# CRYO_ASIC_flex_40pin_adapter.net
KiCad netlist of a schematic drawn in Altium Designer
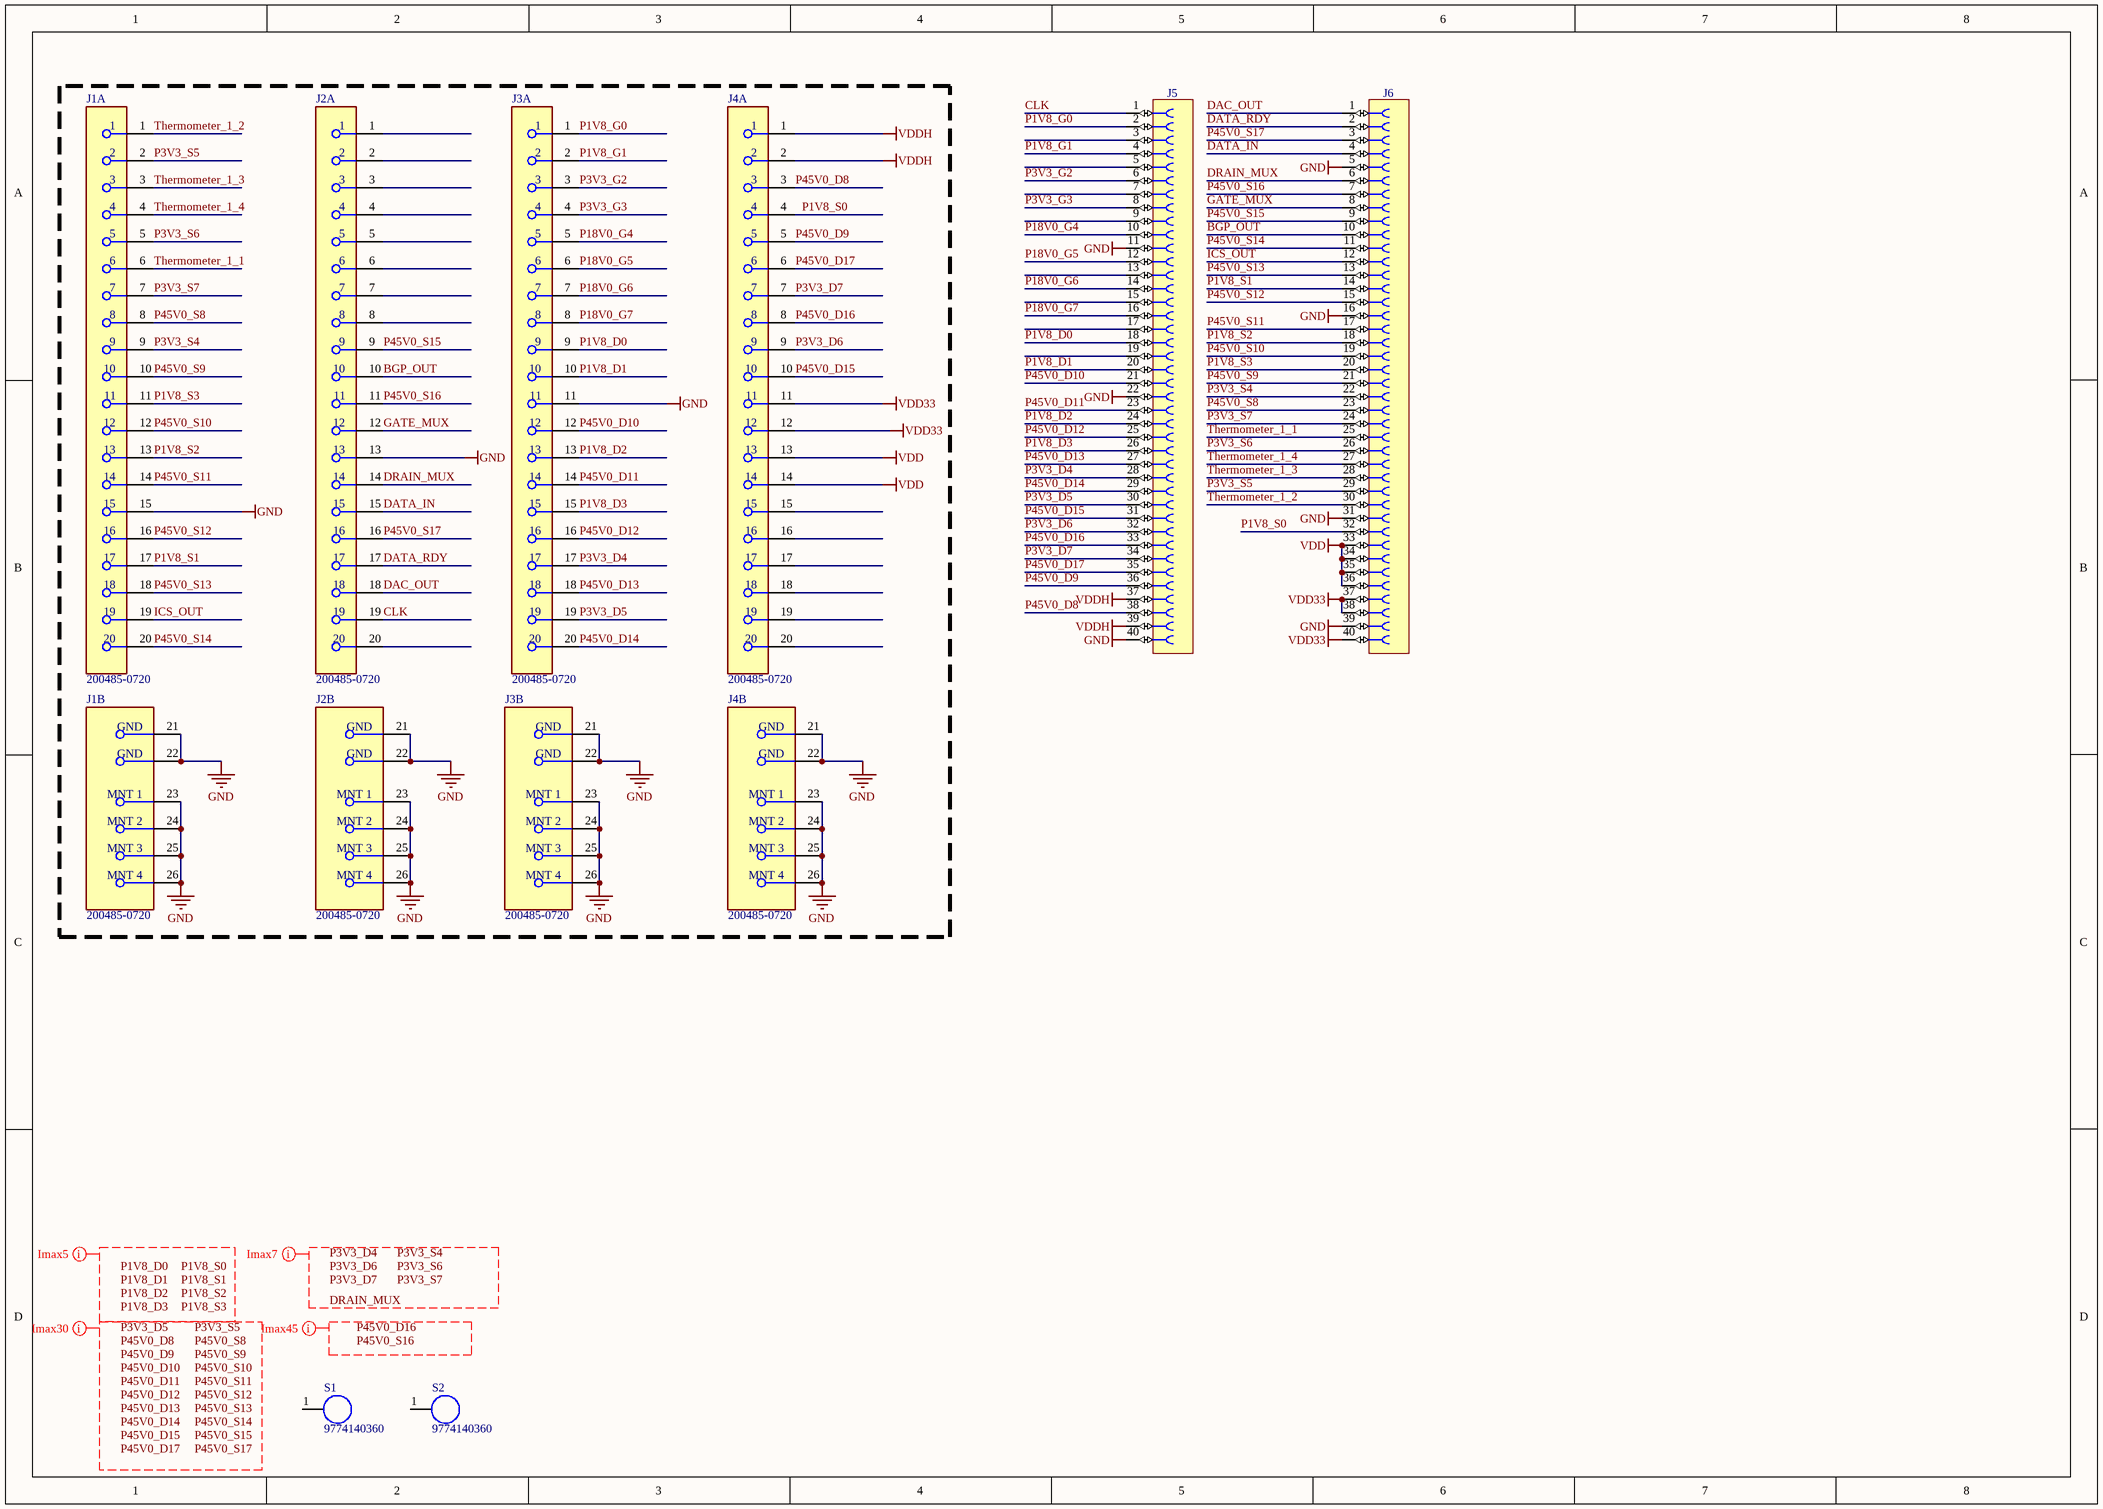
[diagram p0: CRYO_ASIC_flex_40pin_adapter.SchDoc]

(export (version "E")
  (design (tool "Eeschema 10.0.6"))
  (components
    (comp (ref "J1")
      (value "200485-0720")
      (footprint "FP-200485-0720-MFG")
      (description "0.5 ONE-TOUCH ST 20P GND")
      (libsource (lib "Altium Content Vault") (part "ad1b4d674f8db84ba9d04d6195ac6ba"))
    )
    (comp (ref "J2")
      (value "200485-0720")
      (footprint "FP-200485-0720-MFG")
      (description "0.5 ONE-TOUCH ST 20P GND")
      (libsource (lib "Altium Content Vault") (part "ad1b4d674f8db84ba9d04d6195ac6ba"))
    )
    (comp (ref "J3")
      (value "200485-0720")
      (footprint "FP-200485-0720-MFG")
      (description "0.5 ONE-TOUCH ST 20P GND")
      (libsource (lib "Altium Content Vault") (part "ad1b4d674f8db84ba9d04d6195ac6ba"))
    )
    (comp (ref "J4")
      (value "200485-0720")
      (footprint "FP-200485-0720-MFG")
      (description "0.5 ONE-TOUCH ST 20P GND")
      (libsource (lib "Altium Content Vault") (part "ad1b4d674f8db84ba9d04d6195ac6ba"))
    )
    (comp (ref "J5")
      (value "Socket 40")
      (footprint "SAMTEC_RSM-120-02-L-D-K-TR")
      (description "Connector 40 Female")
      (fields
        (field (name "PART NUMBER") "SAMTEC_RSM-120-02-L-D-K-TR")
        (field (name "MANUFACTURER") "SAMTEC")
        (field (name "AUTHOR") "CERN DEM JLC")
      )
      (libsource (lib "Connectors") (part "Connector 40 Female"))
    )
    (comp (ref "J6")
      (value "Socket 40")
      (footprint "SAMTEC_RSM-120-02-L-D-K-TR")
      (description "Connector 40 Female")
      (fields
        (field (name "PART NUMBER") "SAMTEC_RSM-120-02-L-D-K-TR")
        (field (name "MANUFACTURER") "SAMTEC")
        (field (name "AUTHOR") "CERN DEM JLC")
      )
      (libsource (lib "Connectors") (part "Connector 40 Female"))
    )
    (comp (ref "S1")
      (value "9774140360")
      (footprint "9774140360")
      (description "WA-SMSI SMD Steel Spacer with internal Thread")
      (fields (field (name "MANUFACTURER") "Wurth Elektronik") (field (name "CREATED BY") "Baojun Chen"))
      (libsource (lib "Altium_SMSI_SMT_STEEL_SPACER_M2_5_THREAD_INTERNAL_rev15a") (part "WA-SMSI,  9774140360"))
    )
    (comp (ref "S2")
      (value "9774140360")
      (footprint "9774140360")
      (description "WA-SMSI SMD Steel Spacer with internal Thread")
      (fields (field (name "MANUFACTURER") "Wurth Elektronik") (field (name "CREATED BY") "Baojun Chen"))
      (libsource (lib "Altium_SMSI_SMT_STEEL_SPACER_M2_5_THREAD_INTERNAL_rev15a") (part "WA-SMSI,  9774140360"))
    )
  )
  (nets
    (net (code "1") (name "/BGP_OUT") (class "Default")
      (node (ref "J2") (pin "10") (pinfunction "10_10") (pintype "passive"))
      (node (ref "J6") (pin "10") (pinfunction "10_10") (pintype "bidirectional"))
    )
    (net (code "2") (name "/CLK") (class "Default")
      (node (ref "J2") (pin "19") (pinfunction "19_19") (pintype "passive"))
      (node (ref "J5") (pin "1") (pinfunction "1_1") (pintype "bidirectional"))
    )
    (net (code "3") (name "/DAC_OUT") (class "Default")
      (node (ref "J2") (pin "18") (pinfunction "18_18") (pintype "passive"))
      (node (ref "J6") (pin "1") (pinfunction "1_1") (pintype "bidirectional"))
    )
    (net (code "4") (name "/DATA_IN") (class "Default")
      (node (ref "J2") (pin "15") (pinfunction "15_15") (pintype "passive"))
      (node (ref "J6") (pin "4") (pinfunction "4_4") (pintype "bidirectional"))
    )
    (net (code "5") (name "/DATA_RDY") (class "Default")
      (node (ref "J2") (pin "17") (pinfunction "17_17") (pintype "passive"))
      (node (ref "J6") (pin "2") (pinfunction "2_2") (pintype "bidirectional"))
    )
    (net (code "6") (name "/DRAIN_MUX") (class "Default")
      (node (ref "J2") (pin "14") (pinfunction "14_14") (pintype "passive"))
      (node (ref "J6") (pin "6") (pinfunction "6_6") (pintype "bidirectional"))
    )
    (net (code "7") (name "/GATE_MUX") (class "Default")
      (node (ref "J2") (pin "12") (pinfunction "12_12") (pintype "passive"))
      (node (ref "J6") (pin "8") (pinfunction "8_8") (pintype "bidirectional"))
    )
    (net (code "8") (name "/ICS_OUT") (class "Default")
      (node (ref "J1") (pin "19") (pinfunction "19_19") (pintype "passive"))
      (node (ref "J6") (pin "12") (pinfunction "12_12") (pintype "bidirectional"))
    )
    (net (code "9") (name "/P1V8_D0") (class "Default")
      (node (ref "J3") (pin "9") (pinfunction "9_9") (pintype "passive"))
      (node (ref "J5") (pin "18") (pinfunction "18_18") (pintype "bidirectional"))
    )
    (net (code "10") (name "/P1V8_D1") (class "Default")
      (node (ref "J3") (pin "10") (pinfunction "10_10") (pintype "passive"))
      (node (ref "J5") (pin "20") (pinfunction "20_20") (pintype "bidirectional"))
    )
    (net (code "11") (name "/P1V8_D2") (class "Default")
      (node (ref "J3") (pin "13") (pinfunction "13_13") (pintype "passive"))
      (node (ref "J5") (pin "24") (pinfunction "24_24") (pintype "bidirectional"))
    )
    (net (code "12") (name "/P1V8_D3") (class "Default")
      (node (ref "J3") (pin "15") (pinfunction "15_15") (pintype "passive"))
      (node (ref "J5") (pin "26") (pinfunction "26_26") (pintype "bidirectional"))
    )
    (net (code "13") (name "/P1V8_G0") (class "Default")
      (node (ref "J3") (pin "1") (pinfunction "1_1") (pintype "passive"))
      (node (ref "J5") (pin "2") (pinfunction "2_2") (pintype "bidirectional"))
    )
    (net (code "14") (name "/P1V8_G1") (class "Default")
      (node (ref "J3") (pin "2") (pinfunction "2_2") (pintype "passive"))
      (node (ref "J5") (pin "4") (pinfunction "4_4") (pintype "bidirectional"))
    )
    (net (code "15") (name "/P1V8_S0") (class "Default")
      (node (ref "J4") (pin "4") (pinfunction "4_4") (pintype "passive"))
      (node (ref "J6") (pin "32") (pinfunction "32_32") (pintype "bidirectional"))
    )
    (net (code "16") (name "/P1V8_S1") (class "Default")
      (node (ref "J1") (pin "17") (pinfunction "17_17") (pintype "passive"))
      (node (ref "J6") (pin "14") (pinfunction "14_14") (pintype "bidirectional"))
    )
    (net (code "17") (name "/P1V8_S2") (class "Default")
      (node (ref "J1") (pin "13") (pinfunction "13_13") (pintype "passive"))
      (node (ref "J6") (pin "18") (pinfunction "18_18") (pintype "bidirectional"))
    )
    (net (code "18") (name "/P1V8_S3") (class "Default")
      (node (ref "J1") (pin "11") (pinfunction "11_11") (pintype "passive"))
      (node (ref "J6") (pin "20") (pinfunction "20_20") (pintype "bidirectional"))
    )
    (net (code "19") (name "/P3V3_D4") (class "Default")
      (node (ref "J3") (pin "17") (pinfunction "17_17") (pintype "passive"))
      (node (ref "J5") (pin "28") (pinfunction "28_28") (pintype "bidirectional"))
    )
    (net (code "20") (name "/P3V3_D5") (class "Default")
      (node (ref "J3") (pin "19") (pinfunction "19_19") (pintype "passive"))
      (node (ref "J5") (pin "30") (pinfunction "30_30") (pintype "bidirectional"))
    )
    (net (code "21") (name "/P3V3_D6") (class "Default")
      (node (ref "J4") (pin "9") (pinfunction "9_9") (pintype "passive"))
      (node (ref "J5") (pin "32") (pinfunction "32_32") (pintype "bidirectional"))
    )
    (net (code "22") (name "/P3V3_D7") (class "Default")
      (node (ref "J4") (pin "7") (pinfunction "7_7") (pintype "passive"))
      (node (ref "J5") (pin "34") (pinfunction "34_34") (pintype "bidirectional"))
    )
    (net (code "23") (name "/P3V3_G2") (class "Default")
      (node (ref "J3") (pin "3") (pinfunction "3_3") (pintype "passive"))
      (node (ref "J5") (pin "6") (pinfunction "6_6") (pintype "bidirectional"))
    )
    (net (code "24") (name "/P3V3_G3") (class "Default")
      (node (ref "J3") (pin "4") (pinfunction "4_4") (pintype "passive"))
      (node (ref "J5") (pin "8") (pinfunction "8_8") (pintype "bidirectional"))
    )
    (net (code "25") (name "/P3V3_S4") (class "Default")
      (node (ref "J1") (pin "9") (pinfunction "9_9") (pintype "passive"))
      (node (ref "J6") (pin "22") (pinfunction "22_22") (pintype "bidirectional"))
    )
    (net (code "26") (name "/P3V3_S5") (class "Default")
      (node (ref "J1") (pin "2") (pinfunction "2_2") (pintype "passive"))
      (node (ref "J6") (pin "29") (pinfunction "29_29") (pintype "bidirectional"))
    )
    (net (code "27") (name "/P3V3_S6") (class "Default")
      (node (ref "J1") (pin "5") (pinfunction "5_5") (pintype "passive"))
      (node (ref "J6") (pin "26") (pinfunction "26_26") (pintype "bidirectional"))
    )
    (net (code "28") (name "/P3V3_S7") (class "Default")
      (node (ref "J1") (pin "7") (pinfunction "7_7") (pintype "passive"))
      (node (ref "J6") (pin "24") (pinfunction "24_24") (pintype "bidirectional"))
    )
    (net (code "29") (name "/P18V0_G4") (class "Default")
      (node (ref "J3") (pin "5") (pinfunction "5_5") (pintype "passive"))
      (node (ref "J5") (pin "10") (pinfunction "10_10") (pintype "bidirectional"))
    )
    (net (code "30") (name "/P18V0_G5") (class "Default")
      (node (ref "J3") (pin "6") (pinfunction "6_6") (pintype "passive"))
      (node (ref "J5") (pin "12") (pinfunction "12_12") (pintype "bidirectional"))
    )
    (net (code "31") (name "/P18V0_G6") (class "Default")
      (node (ref "J3") (pin "7") (pinfunction "7_7") (pintype "passive"))
      (node (ref "J5") (pin "14") (pinfunction "14_14") (pintype "bidirectional"))
    )
    (net (code "32") (name "/P18V0_G7") (class "Default")
      (node (ref "J3") (pin "8") (pinfunction "8_8") (pintype "passive"))
      (node (ref "J5") (pin "16") (pinfunction "16_16") (pintype "bidirectional"))
    )
    (net (code "33") (name "/P45V0_D8") (class "Default")
      (node (ref "J4") (pin "3") (pinfunction "3_3") (pintype "passive"))
      (node (ref "J5") (pin "38") (pinfunction "38_38") (pintype "bidirectional"))
    )
    (net (code "34") (name "/P45V0_D9") (class "Default")
      (node (ref "J4") (pin "5") (pinfunction "5_5") (pintype "passive"))
      (node (ref "J5") (pin "36") (pinfunction "36_36") (pintype "bidirectional"))
    )
    (net (code "35") (name "/P45V0_D10") (class "Default")
      (node (ref "J3") (pin "12") (pinfunction "12_12") (pintype "passive"))
      (node (ref "J5") (pin "21") (pinfunction "21_21") (pintype "bidirectional"))
    )
    (net (code "36") (name "/P45V0_D11") (class "Default")
      (node (ref "J3") (pin "14") (pinfunction "14_14") (pintype "passive"))
      (node (ref "J5") (pin "23") (pinfunction "23_23") (pintype "bidirectional"))
    )
    (net (code "37") (name "/P45V0_D12") (class "Default")
      (node (ref "J3") (pin "16") (pinfunction "16_16") (pintype "passive"))
      (node (ref "J5") (pin "25") (pinfunction "25_25") (pintype "bidirectional"))
    )
    (net (code "38") (name "/P45V0_D13") (class "Default")
      (node (ref "J3") (pin "18") (pinfunction "18_18") (pintype "passive"))
      (node (ref "J5") (pin "27") (pinfunction "27_27") (pintype "bidirectional"))
    )
    (net (code "39") (name "/P45V0_D14") (class "Default")
      (node (ref "J3") (pin "20") (pinfunction "20_20") (pintype "passive"))
      (node (ref "J5") (pin "29") (pinfunction "29_29") (pintype "bidirectional"))
    )
    (net (code "40") (name "/P45V0_D15") (class "Default")
      (node (ref "J4") (pin "10") (pinfunction "10_10") (pintype "passive"))
      (node (ref "J5") (pin "31") (pinfunction "31_31") (pintype "bidirectional"))
    )
    (net (code "41") (name "/P45V0_D16") (class "Default")
      (node (ref "J4") (pin "8") (pinfunction "8_8") (pintype "passive"))
      (node (ref "J5") (pin "33") (pinfunction "33_33") (pintype "bidirectional"))
    )
    (net (code "42") (name "/P45V0_D17") (class "Default")
      (node (ref "J4") (pin "6") (pinfunction "6_6") (pintype "passive"))
      (node (ref "J5") (pin "35") (pinfunction "35_35") (pintype "bidirectional"))
    )
    (net (code "43") (name "/P45V0_S8") (class "Default")
      (node (ref "J1") (pin "8") (pinfunction "8_8") (pintype "passive"))
      (node (ref "J6") (pin "23") (pinfunction "23_23") (pintype "bidirectional"))
    )
    (net (code "44") (name "/P45V0_S9") (class "Default")
      (node (ref "J1") (pin "10") (pinfunction "10_10") (pintype "passive"))
      (node (ref "J6") (pin "21") (pinfunction "21_21") (pintype "bidirectional"))
    )
    (net (code "45") (name "/P45V0_S10") (class "Default")
      (node (ref "J1") (pin "12") (pinfunction "12_12") (pintype "passive"))
      (node (ref "J6") (pin "19") (pinfunction "19_19") (pintype "bidirectional"))
    )
    (net (code "46") (name "/P45V0_S11") (class "Default")
      (node (ref "J1") (pin "14") (pinfunction "14_14") (pintype "passive"))
      (node (ref "J6") (pin "17") (pinfunction "17_17") (pintype "bidirectional"))
    )
    (net (code "47") (name "/P45V0_S12") (class "Default")
      (node (ref "J1") (pin "16") (pinfunction "16_16") (pintype "passive"))
      (node (ref "J6") (pin "15") (pinfunction "15_15") (pintype "bidirectional"))
    )
    (net (code "48") (name "/P45V0_S13") (class "Default")
      (node (ref "J1") (pin "18") (pinfunction "18_18") (pintype "passive"))
      (node (ref "J6") (pin "13") (pinfunction "13_13") (pintype "bidirectional"))
    )
    (net (code "49") (name "/P45V0_S14") (class "Default")
      (node (ref "J1") (pin "20") (pinfunction "20_20") (pintype "passive"))
      (node (ref "J6") (pin "11") (pinfunction "11_11") (pintype "bidirectional"))
    )
    (net (code "50") (name "/P45V0_S15") (class "Default")
      (node (ref "J2") (pin "9") (pinfunction "9_9") (pintype "passive"))
      (node (ref "J6") (pin "9") (pinfunction "9_9") (pintype "bidirectional"))
    )
    (net (code "51") (name "/P45V0_S16") (class "Default")
      (node (ref "J2") (pin "11") (pinfunction "11_11") (pintype "passive"))
      (node (ref "J6") (pin "7") (pinfunction "7_7") (pintype "bidirectional"))
    )
    (net (code "52") (name "/P45V0_S17") (class "Default")
      (node (ref "J2") (pin "16") (pinfunction "16_16") (pintype "passive"))
      (node (ref "J6") (pin "3") (pinfunction "3_3") (pintype "bidirectional"))
    )
    (net (code "53") (name "/Thermometer_1_1") (class "Default")
      (node (ref "J1") (pin "6") (pinfunction "6_6") (pintype "passive"))
      (node (ref "J6") (pin "25") (pinfunction "25_25") (pintype "bidirectional"))
    )
    (net (code "54") (name "/Thermometer_1_2") (class "Default")
      (node (ref "J1") (pin "1") (pinfunction "1_1") (pintype "passive"))
      (node (ref "J6") (pin "30") (pinfunction "30_30") (pintype "bidirectional"))
    )
    (net (code "55") (name "/Thermometer_1_3") (class "Default")
      (node (ref "J1") (pin "3") (pinfunction "3_3") (pintype "passive"))
      (node (ref "J6") (pin "28") (pinfunction "28_28") (pintype "bidirectional"))
    )
    (net (code "56") (name "/Thermometer_1_4") (class "Default")
      (node (ref "J1") (pin "4") (pinfunction "4_4") (pintype "passive"))
      (node (ref "J6") (pin "27") (pinfunction "27_27") (pintype "bidirectional"))
    )
    (net (code "57") (name "GND") (class "Default")
      (node (ref "J1") (pin "15") (pinfunction "15_15") (pintype "passive"))
      (node (ref "J1") (pin "21") (pinfunction "GND_21") (pintype "power_in"))
      (node (ref "J1") (pin "22") (pinfunction "GND_22") (pintype "power_in"))
      (node (ref "J1") (pin "23") (pinfunction "MNT_1_23") (pintype "passive"))
      (node (ref "J1") (pin "24") (pinfunction "MNT_2_24") (pintype "passive"))
      (node (ref "J1") (pin "25") (pinfunction "MNT_3_25") (pintype "passive"))
      (node (ref "J1") (pin "26") (pinfunction "MNT_4_26") (pintype "passive"))
      (node (ref "J2") (pin "13") (pinfunction "13_13") (pintype "passive"))
      (node (ref "J2") (pin "21") (pinfunction "GND_21") (pintype "power_in"))
      (node (ref "J2") (pin "22") (pinfunction "GND_22") (pintype "power_in"))
      (node (ref "J2") (pin "23") (pinfunction "MNT_1_23") (pintype "passive"))
      (node (ref "J2") (pin "24") (pinfunction "MNT_2_24") (pintype "passive"))
      (node (ref "J2") (pin "25") (pinfunction "MNT_3_25") (pintype "passive"))
      (node (ref "J2") (pin "26") (pinfunction "MNT_4_26") (pintype "passive"))
      (node (ref "J3") (pin "11") (pinfunction "11_11") (pintype "passive"))
      (node (ref "J3") (pin "21") (pinfunction "GND_21") (pintype "power_in"))
      (node (ref "J3") (pin "22") (pinfunction "GND_22") (pintype "power_in"))
      (node (ref "J3") (pin "23") (pinfunction "MNT_1_23") (pintype "passive"))
      (node (ref "J3") (pin "24") (pinfunction "MNT_2_24") (pintype "passive"))
      (node (ref "J3") (pin "25") (pinfunction "MNT_3_25") (pintype "passive"))
      (node (ref "J3") (pin "26") (pinfunction "MNT_4_26") (pintype "passive"))
      (node (ref "J4") (pin "21") (pinfunction "GND_21") (pintype "power_in"))
      (node (ref "J4") (pin "22") (pinfunction "GND_22") (pintype "power_in"))
      (node (ref "J4") (pin "23") (pinfunction "MNT_1_23") (pintype "passive"))
      (node (ref "J4") (pin "24") (pinfunction "MNT_2_24") (pintype "passive"))
      (node (ref "J4") (pin "25") (pinfunction "MNT_3_25") (pintype "passive"))
      (node (ref "J4") (pin "26") (pinfunction "MNT_4_26") (pintype "passive"))
      (node (ref "J5") (pin "11") (pinfunction "11_11") (pintype "bidirectional"))
      (node (ref "J5") (pin "22") (pinfunction "22_22") (pintype "bidirectional"))
      (node (ref "J5") (pin "40") (pinfunction "40_40") (pintype "bidirectional"))
      (node (ref "J6") (pin "16") (pinfunction "16_16") (pintype "bidirectional"))
      (node (ref "J6") (pin "31") (pinfunction "31_31") (pintype "bidirectional"))
      (node (ref "J6") (pin "39") (pinfunction "39_39") (pintype "bidirectional"))
      (node (ref "J6") (pin "5") (pinfunction "5_5") (pintype "bidirectional"))
    )
    (net (code "58") (name "VDD") (class "Default")
      (node (ref "J4") (pin "13") (pinfunction "13_13") (pintype "passive"))
      (node (ref "J4") (pin "14") (pinfunction "14_14") (pintype "passive"))
      (node (ref "J6") (pin "33") (pinfunction "33_33") (pintype "bidirectional"))
      (node (ref "J6") (pin "34") (pinfunction "34_34") (pintype "bidirectional"))
      (node (ref "J6") (pin "35") (pinfunction "35_35") (pintype "bidirectional"))
      (node (ref "J6") (pin "36") (pinfunction "36_36") (pintype "bidirectional"))
    )
    (net (code "59") (name "VDD33") (class "Default")
      (node (ref "J4") (pin "11") (pinfunction "11_11") (pintype "passive"))
      (node (ref "J4") (pin "12") (pinfunction "12_12") (pintype "passive"))
      (node (ref "J6") (pin "37") (pinfunction "37_37") (pintype "bidirectional"))
      (node (ref "J6") (pin "38") (pinfunction "38_38") (pintype "bidirectional"))
      (node (ref "J6") (pin "40") (pinfunction "40_40") (pintype "bidirectional"))
    )
    (net (code "60") (name "VDDH") (class "Default")
      (node (ref "J4") (pin "1") (pinfunction "1_1") (pintype "passive"))
      (node (ref "J4") (pin "2") (pinfunction "2_2") (pintype "passive"))
      (node (ref "J5") (pin "37") (pinfunction "37_37") (pintype "bidirectional"))
      (node (ref "J5") (pin "39") (pinfunction "39_39") (pintype "bidirectional"))
    )
    (net (code "61") (name "unconnected-(J2-Pad1)") (class "Default")
      (node (ref "J2") (pin "1") (pinfunction "1_1") (pintype "passive"))
    )
    (net (code "62") (name "unconnected-(J2-Pad2)") (class "Default")
      (node (ref "J2") (pin "2") (pinfunction "2_2") (pintype "passive"))
    )
    (net (code "63") (name "unconnected-(J2-Pad3)") (class "Default")
      (node (ref "J2") (pin "3") (pinfunction "3_3") (pintype "passive"))
    )
    (net (code "64") (name "unconnected-(J2-Pad4)") (class "Default")
      (node (ref "J2") (pin "4") (pinfunction "4_4") (pintype "passive"))
    )
    (net (code "65") (name "unconnected-(J2-Pad5)") (class "Default")
      (node (ref "J2") (pin "5") (pinfunction "5_5") (pintype "passive"))
    )
    (net (code "66") (name "unconnected-(J2-Pad6)") (class "Default")
      (node (ref "J2") (pin "6") (pinfunction "6_6") (pintype "passive"))
    )
    (net (code "67") (name "unconnected-(J2-Pad7)") (class "Default")
      (node (ref "J2") (pin "7") (pinfunction "7_7") (pintype "passive"))
    )
    (net (code "68") (name "unconnected-(J2-Pad8)") (class "Default")
      (node (ref "J2") (pin "8") (pinfunction "8_8") (pintype "passive"))
    )
    (net (code "69") (name "unconnected-(J2-Pad20)") (class "Default")
      (node (ref "J2") (pin "20") (pinfunction "20_20") (pintype "passive"))
    )
    (net (code "70") (name "unconnected-(J4-Pad15)") (class "Default")
      (node (ref "J4") (pin "15") (pinfunction "15_15") (pintype "passive"))
    )
    (net (code "71") (name "unconnected-(J4-Pad16)") (class "Default")
      (node (ref "J4") (pin "16") (pinfunction "16_16") (pintype "passive"))
    )
    (net (code "72") (name "unconnected-(J4-Pad17)") (class "Default")
      (node (ref "J4") (pin "17") (pinfunction "17_17") (pintype "passive"))
    )
    (net (code "73") (name "unconnected-(J4-Pad18)") (class "Default")
      (node (ref "J4") (pin "18") (pinfunction "18_18") (pintype "passive"))
    )
    (net (code "74") (name "unconnected-(J4-Pad19)") (class "Default")
      (node (ref "J4") (pin "19") (pinfunction "19_19") (pintype "passive"))
    )
    (net (code "75") (name "unconnected-(J4-Pad20)") (class "Default")
      (node (ref "J4") (pin "20") (pinfunction "20_20") (pintype "passive"))
    )
    (net (code "76") (name "unconnected-(J5-Pad3)") (class "Default")
      (node (ref "J5") (pin "3") (pinfunction "3_3") (pintype "bidirectional"))
    )
    (net (code "77") (name "unconnected-(J5-Pad5)") (class "Default")
      (node (ref "J5") (pin "5") (pinfunction "5_5") (pintype "bidirectional"))
    )
    (net (code "78") (name "unconnected-(J5-Pad7)") (class "Default")
      (node (ref "J5") (pin "7") (pinfunction "7_7") (pintype "bidirectional"))
    )
    (net (code "79") (name "unconnected-(J5-Pad9)") (class "Default")
      (node (ref "J5") (pin "9") (pinfunction "9_9") (pintype "bidirectional"))
    )
    (net (code "80") (name "unconnected-(J5-Pad13)") (class "Default")
      (node (ref "J5") (pin "13") (pinfunction "13_13") (pintype "bidirectional"))
    )
    (net (code "81") (name "unconnected-(J5-Pad15)") (class "Default")
      (node (ref "J5") (pin "15") (pinfunction "15_15") (pintype "bidirectional"))
    )
    (net (code "82") (name "unconnected-(J5-Pad17)") (class "Default")
      (node (ref "J5") (pin "17") (pinfunction "17_17") (pintype "bidirectional"))
    )
    (net (code "83") (name "unconnected-(J5-Pad19)") (class "Default")
      (node (ref "J5") (pin "19") (pinfunction "19_19") (pintype "bidirectional"))
    )
    (net (code "84") (name "unconnected-(S1-Pad1)") (class "Default")
      (node (ref "S1") (pin "1") (pinfunction "1_1") (pintype "passive"))
    )
    (net (code "85") (name "unconnected-(S2-Pad1)") (class "Default")
      (node (ref "S2") (pin "1") (pinfunction "1_1") (pintype "passive"))
    )
  )
)
